# Modulator.net
KiCad netlist of a schematic drawn in Altium Designer
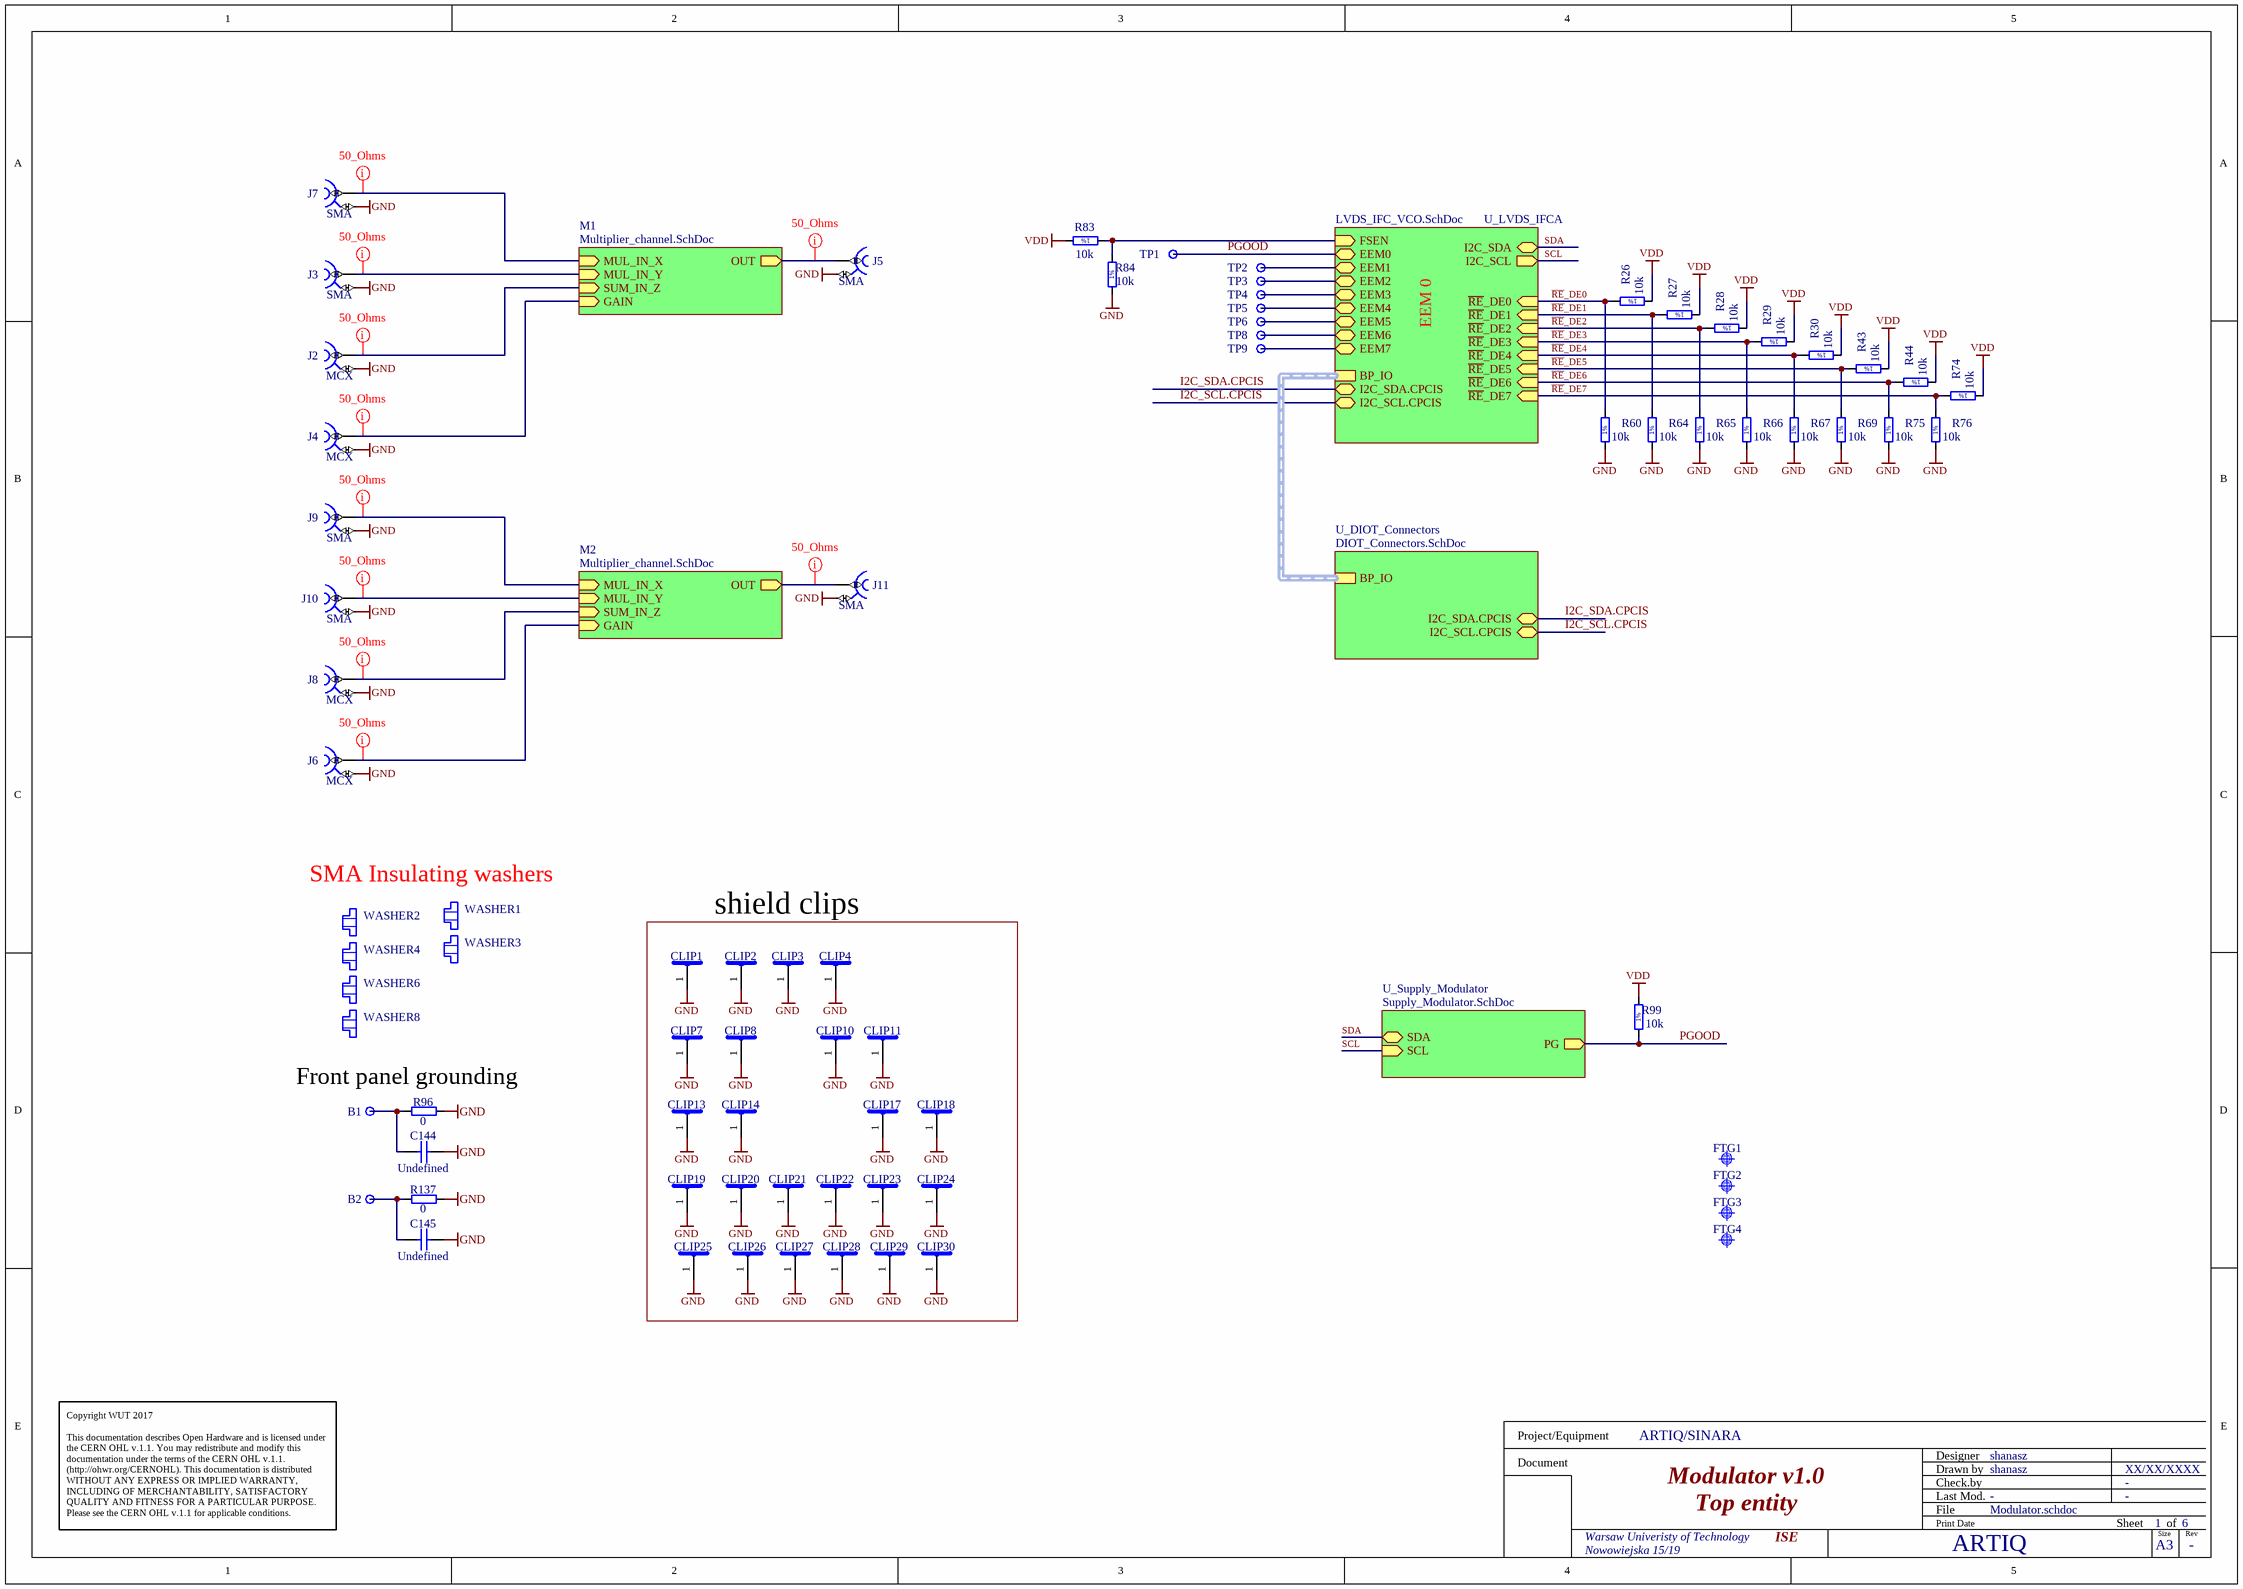
[diagram p0: Modulator.schdoc]

(export (version "E")
  (design (tool "Eeschema 10.0.6"))
  (components
    (comp (ref "B1")
      (value "Plated Hole")
      (footprint "MTG270_500")
      (description "Single Terminal Socket")
      (fields (field (name "PART NUMBER") "PLATED_HOLE2.7_PAD5.0") (field (name "AUTHOR") "CERN DEM JMW"))
      (libsource (lib "Eletro-mechanical") (part "Single Terminal Socket"))
    )
    (comp (ref "B2")
      (value "Plated Hole")
      (footprint "MTG270_500")
      (description "Single Terminal Socket")
      (fields (field (name "PART NUMBER") "PLATED_HOLE2.7_PAD5.0") (field (name "AUTHOR") "CERN DEM JMW"))
      (libsource (lib "Eletro-mechanical") (part "Single Terminal Socket"))
    )
    (comp (ref "C144")
      (value "Undefined")
      (footprint "CAPC2012X135N")
      (description "Non-polarised capacitor")
      (fields (field (name "PART NUMBER") "CC0805_NO-VALUE") (field (name "AUTHOR") "CERN DEM JLC"))
      (libsource (lib "Capacitors") (part "Capacitor - non polarized"))
    )
    (comp (ref "C145")
      (value "Undefined")
      (footprint "CAPC2012X135N")
      (description "Non-polarised capacitor")
      (fields (field (name "PART NUMBER") "CC0805_NO-VALUE") (field (name "AUTHOR") "CERN DEM JLC"))
      (libsource (lib "Capacitors") (part "Capacitor - non polarized"))
    )
    (comp (ref "CLIP1")
      (value "S1411-46R")
      (footprint "CLIP_HOLLAND-SHIELDING_LC")
      (description "Surface Mount Clip for PCB Screening Covers")
      (fields (field (name "MANUFACTURER") "HARWIN") (field (name "AUTHOR") "CERN DEM JLC"))
      (libsource (lib "LIBRARY_SCH") (part "SHIELD_CLIP"))
    )
    (comp (ref "CLIP2")
      (value "S1411-46R")
      (footprint "CLIP_HOLLAND-SHIELDING_LC")
      (description "Surface Mount Clip for PCB Screening Covers")
      (fields (field (name "MANUFACTURER") "HARWIN") (field (name "AUTHOR") "CERN DEM JLC"))
      (libsource (lib "LIBRARY_SCH") (part "SHIELD_CLIP"))
    )
    (comp (ref "CLIP3")
      (value "S1411-46R")
      (footprint "CLIP_HOLLAND-SHIELDING_LC")
      (description "Surface Mount Clip for PCB Screening Covers")
      (fields (field (name "MANUFACTURER") "HARWIN") (field (name "AUTHOR") "CERN DEM JLC"))
      (libsource (lib "LIBRARY_SCH") (part "SHIELD_CLIP"))
    )
    (comp (ref "CLIP4")
      (value "S1411-46R")
      (footprint "CLIP_HOLLAND-SHIELDING_LC")
      (description "Surface Mount Clip for PCB Screening Covers")
      (fields (field (name "MANUFACTURER") "HARWIN") (field (name "AUTHOR") "CERN DEM JLC"))
      (libsource (lib "LIBRARY_SCH") (part "SHIELD_CLIP"))
    )
    (comp (ref "CLIP7")
      (value "S1411-46R")
      (footprint "CLIP_HOLLAND-SHIELDING_LC")
      (description "Surface Mount Clip for PCB Screening Covers")
      (fields (field (name "MANUFACTURER") "HARWIN") (field (name "AUTHOR") "CERN DEM JLC"))
      (libsource (lib "LIBRARY_SCH") (part "SHIELD_CLIP"))
    )
    (comp (ref "CLIP8")
      (value "S1411-46R")
      (footprint "CLIP_HOLLAND-SHIELDING_LC")
      (description "Surface Mount Clip for PCB Screening Covers")
      (fields (field (name "MANUFACTURER") "HARWIN") (field (name "AUTHOR") "CERN DEM JLC"))
      (libsource (lib "LIBRARY_SCH") (part "SHIELD_CLIP"))
    )
    (comp (ref "CLIP10")
      (value "S1411-46R")
      (footprint "CLIP_HOLLAND-SHIELDING_LC")
      (description "Surface Mount Clip for PCB Screening Covers")
      (fields (field (name "MANUFACTURER") "HARWIN") (field (name "AUTHOR") "CERN DEM JLC"))
      (libsource (lib "LIBRARY_SCH") (part "SHIELD_CLIP"))
    )
    (comp (ref "CLIP11")
      (value "S1411-46R")
      (footprint "CLIP_HOLLAND-SHIELDING_LC")
      (description "Surface Mount Clip for PCB Screening Covers")
      (fields (field (name "MANUFACTURER") "HARWIN") (field (name "AUTHOR") "CERN DEM JLC"))
      (libsource (lib "LIBRARY_SCH") (part "SHIELD_CLIP"))
    )
    (comp (ref "CLIP13")
      (value "S1411-46R")
      (footprint "CLIP_HOLLAND-SHIELDING_LC")
      (description "Surface Mount Clip for PCB Screening Covers")
      (fields (field (name "MANUFACTURER") "HARWIN") (field (name "AUTHOR") "CERN DEM JLC"))
      (libsource (lib "LIBRARY_SCH") (part "SHIELD_CLIP"))
    )
    (comp (ref "CLIP14")
      (value "S1411-46R")
      (footprint "CLIP_HOLLAND-SHIELDING_LC")
      (description "Surface Mount Clip for PCB Screening Covers")
      (fields (field (name "MANUFACTURER") "HARWIN") (field (name "AUTHOR") "CERN DEM JLC"))
      (libsource (lib "LIBRARY_SCH") (part "SHIELD_CLIP"))
    )
    (comp (ref "CLIP17")
      (value "S1411-46R")
      (footprint "CLIP_HOLLAND-SHIELDING_LC")
      (description "Surface Mount Clip for PCB Screening Covers")
      (fields (field (name "MANUFACTURER") "HARWIN") (field (name "AUTHOR") "CERN DEM JLC"))
      (libsource (lib "LIBRARY_SCH") (part "SHIELD_CLIP"))
    )
    (comp (ref "CLIP18")
      (value "S1411-46R")
      (footprint "CLIP_HOLLAND-SHIELDING_LC")
      (description "Surface Mount Clip for PCB Screening Covers")
      (fields (field (name "MANUFACTURER") "HARWIN") (field (name "AUTHOR") "CERN DEM JLC"))
      (libsource (lib "LIBRARY_SCH") (part "SHIELD_CLIP"))
    )
    (comp (ref "CLIP19")
      (value "S1411-46R")
      (footprint "CLIP_HOLLAND-SHIELDING_LC")
      (description "Surface Mount Clip for PCB Screening Covers")
      (fields (field (name "MANUFACTURER") "HARWIN") (field (name "AUTHOR") "CERN DEM JLC"))
      (libsource (lib "LIBRARY_SCH") (part "SHIELD_CLIP"))
    )
    (comp (ref "CLIP20")
      (value "S1411-46R")
      (footprint "CLIP_HOLLAND-SHIELDING_LC")
      (description "Surface Mount Clip for PCB Screening Covers")
      (fields (field (name "MANUFACTURER") "HARWIN") (field (name "AUTHOR") "CERN DEM JLC"))
      (libsource (lib "LIBRARY_SCH") (part "SHIELD_CLIP"))
    )
    (comp (ref "CLIP21")
      (value "S1411-46R")
      (footprint "CLIP_HOLLAND-SHIELDING_LC")
      (description "Surface Mount Clip for PCB Screening Covers")
      (fields (field (name "MANUFACTURER") "HARWIN") (field (name "AUTHOR") "CERN DEM JLC"))
      (libsource (lib "LIBRARY_SCH") (part "SHIELD_CLIP"))
    )
    (comp (ref "CLIP22")
      (value "S1411-46R")
      (footprint "CLIP_HOLLAND-SHIELDING_LC")
      (description "Surface Mount Clip for PCB Screening Covers")
      (fields (field (name "MANUFACTURER") "HARWIN") (field (name "AUTHOR") "CERN DEM JLC"))
      (libsource (lib "LIBRARY_SCH") (part "SHIELD_CLIP"))
    )
    (comp (ref "CLIP23")
      (value "S1411-46R")
      (footprint "CLIP_HOLLAND-SHIELDING_LC")
      (description "Surface Mount Clip for PCB Screening Covers")
      (fields (field (name "MANUFACTURER") "HARWIN") (field (name "AUTHOR") "CERN DEM JLC"))
      (libsource (lib "LIBRARY_SCH") (part "SHIELD_CLIP"))
    )
    (comp (ref "CLIP24")
      (value "S1411-46R")
      (footprint "CLIP_HOLLAND-SHIELDING_LC")
      (description "Surface Mount Clip for PCB Screening Covers")
      (fields (field (name "MANUFACTURER") "HARWIN") (field (name "AUTHOR") "CERN DEM JLC"))
      (libsource (lib "LIBRARY_SCH") (part "SHIELD_CLIP"))
    )
    (comp (ref "CLIP25")
      (value "S1411-46R")
      (footprint "CLIP_HOLLAND-SHIELDING_LC")
      (description "Surface Mount Clip for PCB Screening Covers")
      (fields (field (name "MANUFACTURER") "HARWIN") (field (name "AUTHOR") "CERN DEM JLC"))
      (libsource (lib "LIBRARY_SCH") (part "SHIELD_CLIP"))
    )
    (comp (ref "CLIP26")
      (value "S1411-46R")
      (footprint "CLIP_HOLLAND-SHIELDING_LC")
      (description "Surface Mount Clip for PCB Screening Covers")
      (fields (field (name "MANUFACTURER") "HARWIN") (field (name "AUTHOR") "CERN DEM JLC"))
      (libsource (lib "LIBRARY_SCH") (part "SHIELD_CLIP"))
    )
    (comp (ref "CLIP27")
      (value "S1411-46R")
      (footprint "CLIP_HOLLAND-SHIELDING_LC")
      (description "Surface Mount Clip for PCB Screening Covers")
      (fields (field (name "MANUFACTURER") "HARWIN") (field (name "AUTHOR") "CERN DEM JLC"))
      (libsource (lib "LIBRARY_SCH") (part "SHIELD_CLIP"))
    )
    (comp (ref "CLIP28")
      (value "S1411-46R")
      (footprint "CLIP_HOLLAND-SHIELDING_LC")
      (description "Surface Mount Clip for PCB Screening Covers")
      (fields (field (name "MANUFACTURER") "HARWIN") (field (name "AUTHOR") "CERN DEM JLC"))
      (libsource (lib "LIBRARY_SCH") (part "SHIELD_CLIP"))
    )
    (comp (ref "CLIP29")
      (value "S1411-46R")
      (footprint "CLIP_HOLLAND-SHIELDING_LC")
      (description "Surface Mount Clip for PCB Screening Covers")
      (fields (field (name "MANUFACTURER") "HARWIN") (field (name "AUTHOR") "CERN DEM JLC"))
      (libsource (lib "LIBRARY_SCH") (part "SHIELD_CLIP"))
    )
    (comp (ref "CLIP30")
      (value "S1411-46R")
      (footprint "CLIP_HOLLAND-SHIELDING_LC")
      (description "Surface Mount Clip for PCB Screening Covers")
      (fields (field (name "MANUFACTURER") "HARWIN") (field (name "AUTHOR") "CERN DEM JLC"))
      (libsource (lib "LIBRARY_SCH") (part "SHIELD_CLIP"))
    )
    (comp (ref "FTG1")
      (value "Use only in PCB")
      (footprint "FIDUCIAL_TOP_C100-200")
      (description "Fiducial Target")
      (fields (field (name "PART NUMBER") "FIDUCIAL_TARGET_C100-200") (field (name "AUTHOR") "CERN DEM JLC"))
      (libsource (lib "Eletro-mechanical") (part "Fiducial Target"))
    )
    (comp (ref "FTG2")
      (value "Use only in PCB")
      (footprint "FIDUCIAL_TOP_S100-200")
      (description "Fiducial Target")
      (fields (field (name "PART NUMBER") "FIDUCIAL_TARGET_S100-200") (field (name "AUTHOR") "CERN DEM JLC"))
      (libsource (lib "Eletro-mechanical") (part "Fiducial Target"))
    )
    (comp (ref "FTG3")
      (value "Use only in PCB")
      (footprint "FIDUCIAL_TOP_S200-400")
      (description "Fiducial Target")
      (fields (field (name "PART NUMBER") "FIDUCIAL_TARGET_S200-400") (field (name "AUTHOR") "CERN DEM JLC"))
      (libsource (lib "Eletro-mechanical") (part "Fiducial Target"))
    )
    (comp (ref "FTG4")
      (value "Use only in PCB")
      (footprint "FIDUCIAL_TOP_S100-200")
      (description "Fiducial Target")
      (fields (field (name "PART NUMBER") "FIDUCIAL_TARGET_S100-200") (field (name "AUTHOR") "CERN DEM JLC"))
      (libsource (lib "Eletro-mechanical") (part "Fiducial Target"))
    )
    (comp (ref "J2")
      (value "MCX")
      (footprint "AMPHENOL_919-383J-51A")
      (fields
        (field (name "PART NUMBER") "AMPHENOL_919-383J-51A")
        (field (name "MANUFACTURER") "AMPHENOL")
        (field (name "MANUFACTURER PART NUMBER") "919-383J-51A")
        (field (name "AUTHOR") "CERN DEM BC")
      )
      (libsource (lib "Connectors") (part "Coax_1Female_1Shield"))
    )
    (comp (ref "J3")
      (value "SMA")
      (footprint "DELOCK_65848")
      (description "50 Ohm Through Hole SMA Right Angle PCB Jack")
      (fields
        (field (name "PART NUMBER") "DELOCK_65848")
        (field (name "MANUFACTURER") "DELOCK")
        (field (name "AUTHOR") "GK")
      )
      (libsource (lib "Modulator_pLib") (part "CON_SMA_DELOCK_65848"))
    )
    (comp (ref "J4")
      (value "MCX")
      (footprint "AMPHENOL_919-383J-51A")
      (fields
        (field (name "PART NUMBER") "AMPHENOL_919-383J-51A")
        (field (name "MANUFACTURER") "AMPHENOL")
        (field (name "MANUFACTURER PART NUMBER") "919-383J-51A")
        (field (name "AUTHOR") "CERN DEM BC")
      )
      (libsource (lib "Connectors") (part "Coax_1Female_1Shield"))
    )
    (comp (ref "J5")
      (value "SMA")
      (footprint "DELOCK_65848")
      (description "50 Ohm Through Hole SMA Right Angle PCB Jack")
      (fields
        (field (name "PART NUMBER") "DELOCK_65848")
        (field (name "MANUFACTURER") "DELOCK")
        (field (name "AUTHOR") "GK")
      )
      (libsource (lib "") (part "CON_SMA_DELOCK_65848_1"))
    )
    (comp (ref "J6")
      (value "MCX")
      (footprint "AMPHENOL_919-383J-51A")
      (fields
        (field (name "PART NUMBER") "AMPHENOL_919-383J-51A")
        (field (name "MANUFACTURER") "AMPHENOL")
        (field (name "MANUFACTURER PART NUMBER") "919-383J-51A")
        (field (name "AUTHOR") "CERN DEM BC")
      )
      (libsource (lib "Connectors") (part "Coax_1Female_1Shield"))
    )
    (comp (ref "J7")
      (value "SMA")
      (footprint "DELOCK_65848")
      (description "50 Ohm Through Hole SMA Right Angle PCB Jack")
      (fields
        (field (name "PART NUMBER") "DELOCK_65848")
        (field (name "MANUFACTURER") "DELOCK")
        (field (name "AUTHOR") "GK")
      )
      (libsource (lib "Modulator_pLib") (part "CON_SMA_DELOCK_65848"))
    )
    (comp (ref "J8")
      (value "MCX")
      (footprint "AMPHENOL_919-383J-51A")
      (fields
        (field (name "PART NUMBER") "AMPHENOL_919-383J-51A")
        (field (name "MANUFACTURER") "AMPHENOL")
        (field (name "MANUFACTURER PART NUMBER") "919-383J-51A")
        (field (name "AUTHOR") "CERN DEM BC")
      )
      (libsource (lib "Connectors") (part "Coax_1Female_1Shield"))
    )
    (comp (ref "J9")
      (value "SMA")
      (footprint "DELOCK_65848")
      (description "50 Ohm Through Hole SMA Right Angle PCB Jack")
      (fields
        (field (name "PART NUMBER") "DELOCK_65848")
        (field (name "MANUFACTURER") "DELOCK")
        (field (name "AUTHOR") "GK")
      )
      (libsource (lib "Modulator_pLib") (part "CON_SMA_DELOCK_65848"))
    )
    (comp (ref "J10")
      (value "SMA")
      (footprint "DELOCK_65848")
      (description "50 Ohm Through Hole SMA Right Angle PCB Jack")
      (fields
        (field (name "PART NUMBER") "DELOCK_65848")
        (field (name "MANUFACTURER") "DELOCK")
        (field (name "AUTHOR") "GK")
      )
      (libsource (lib "Modulator_pLib") (part "CON_SMA_DELOCK_65848"))
    )
    (comp (ref "J11")
      (value "SMA")
      (footprint "DELOCK_65848")
      (description "50 Ohm Through Hole SMA Right Angle PCB Jack")
      (fields
        (field (name "PART NUMBER") "DELOCK_65848")
        (field (name "MANUFACTURER") "DELOCK")
        (field (name "AUTHOR") "GK")
      )
      (libsource (lib "") (part "CON_SMA_DELOCK_65848_1"))
    )
    (comp (ref "R26")
      (value "10k")
      (footprint "RESC1005X40N")
      (description "Resistor - 1%")
      (fields
        (field (name "PART NUMBER") "R0402_10K_1%_0.0625W_100PPM")
        (field (name "POWER") "0.0625W")
        (field (name "AUTHOR") "CERN DEM JLC")
      )
      (libsource (lib "Resistors") (part "Resistor - 1%"))
    )
    (comp (ref "R27")
      (value "10k")
      (footprint "RESC1005X40N")
      (description "Resistor - 1%")
      (fields
        (field (name "PART NUMBER") "R0402_10K_1%_0.0625W_100PPM")
        (field (name "POWER") "0.0625W")
        (field (name "AUTHOR") "CERN DEM JLC")
      )
      (libsource (lib "Resistors") (part "Resistor - 1%"))
    )
    (comp (ref "R28")
      (value "10k")
      (footprint "RESC1005X40N")
      (description "Resistor - 1%")
      (fields
        (field (name "PART NUMBER") "R0402_10K_1%_0.0625W_100PPM")
        (field (name "POWER") "0.0625W")
        (field (name "AUTHOR") "CERN DEM JLC")
      )
      (libsource (lib "Resistors") (part "Resistor - 1%"))
    )
    (comp (ref "R29")
      (value "10k")
      (footprint "RESC1005X40N")
      (description "Resistor - 1%")
      (fields
        (field (name "PART NUMBER") "R0402_10K_1%_0.0625W_100PPM")
        (field (name "POWER") "0.0625W")
        (field (name "AUTHOR") "CERN DEM JLC")
      )
      (libsource (lib "Resistors") (part "Resistor - 1%"))
    )
    (comp (ref "R30")
      (value "10k")
      (footprint "RESC1005X40N")
      (description "Resistor - 1%")
      (fields
        (field (name "PART NUMBER") "R0402_10K_1%_0.0625W_100PPM")
        (field (name "POWER") "0.0625W")
        (field (name "AUTHOR") "CERN DEM JLC")
      )
      (libsource (lib "Resistors") (part "Resistor - 1%"))
    )
    (comp (ref "R43")
      (value "10k")
      (footprint "RESC1005X40N")
      (description "Resistor - 1%")
      (fields
        (field (name "PART NUMBER") "R0402_10K_1%_0.0625W_100PPM")
        (field (name "POWER") "0.0625W")
        (field (name "AUTHOR") "CERN DEM JLC")
      )
      (libsource (lib "Resistors") (part "Resistor - 1%"))
    )
    (comp (ref "R44")
      (value "10k")
      (footprint "RESC1005X40N")
      (description "Resistor - 1%")
      (fields
        (field (name "PART NUMBER") "R0402_10K_1%_0.0625W_100PPM")
        (field (name "POWER") "0.0625W")
        (field (name "AUTHOR") "CERN DEM JLC")
      )
      (libsource (lib "Resistors") (part "Resistor - 1%"))
    )
    (comp (ref "R60")
      (value "10k")
      (footprint "RESC1005X40N")
      (description "Resistor - 1%")
      (fields
        (field (name "PART NUMBER") "R0402_10K_1%_0.0625W_100PPM")
        (field (name "POWER") "0.0625W")
        (field (name "AUTHOR") "CERN DEM JLC")
      )
      (libsource (lib "Resistors") (part "Resistor - 1%"))
    )
    (comp (ref "R64")
      (value "10k")
      (footprint "RESC1005X40N")
      (description "Resistor - 1%")
      (fields
        (field (name "PART NUMBER") "R0402_10K_1%_0.0625W_100PPM")
        (field (name "POWER") "0.0625W")
        (field (name "AUTHOR") "CERN DEM JLC")
      )
      (libsource (lib "Resistors") (part "Resistor - 1%"))
    )
    (comp (ref "R65")
      (value "10k")
      (footprint "RESC1005X40N")
      (description "Resistor - 1%")
      (fields
        (field (name "PART NUMBER") "R0402_10K_1%_0.0625W_100PPM")
        (field (name "POWER") "0.0625W")
        (field (name "AUTHOR") "CERN DEM JLC")
      )
      (libsource (lib "Resistors") (part "Resistor - 1%"))
    )
    (comp (ref "R66")
      (value "10k")
      (footprint "RESC1005X40N")
      (description "Resistor - 1%")
      (fields
        (field (name "PART NUMBER") "R0402_10K_1%_0.0625W_100PPM")
        (field (name "POWER") "0.0625W")
        (field (name "AUTHOR") "CERN DEM JLC")
      )
      (libsource (lib "Resistors") (part "Resistor - 1%"))
    )
    (comp (ref "R67")
      (value "10k")
      (footprint "RESC1005X40N")
      (description "Resistor - 1%")
      (fields
        (field (name "PART NUMBER") "R0402_10K_1%_0.0625W_100PPM")
        (field (name "POWER") "0.0625W")
        (field (name "AUTHOR") "CERN DEM JLC")
      )
      (libsource (lib "Resistors") (part "Resistor - 1%"))
    )
    (comp (ref "R69")
      (value "10k")
      (footprint "RESC1005X40N")
      (description "Resistor - 1%")
      (fields
        (field (name "PART NUMBER") "R0402_10K_1%_0.0625W_100PPM")
        (field (name "POWER") "0.0625W")
        (field (name "AUTHOR") "CERN DEM JLC")
      )
      (libsource (lib "Resistors") (part "Resistor - 1%"))
    )
    (comp (ref "R74")
      (value "10k")
      (footprint "RESC1005X40N")
      (description "Resistor - 1%")
      (fields
        (field (name "PART NUMBER") "R0402_10K_1%_0.0625W_100PPM")
        (field (name "POWER") "0.0625W")
        (field (name "AUTHOR") "CERN DEM JLC")
      )
      (libsource (lib "Resistors") (part "Resistor - 1%"))
    )
    (comp (ref "R75")
      (value "10k")
      (footprint "RESC1005X40N")
      (description "Resistor - 1%")
      (fields
        (field (name "PART NUMBER") "R0402_10K_1%_0.0625W_100PPM")
        (field (name "POWER") "0.0625W")
        (field (name "AUTHOR") "CERN DEM JLC")
      )
      (libsource (lib "Resistors") (part "Resistor - 1%"))
    )
    (comp (ref "R76")
      (value "10k")
      (footprint "RESC1005X40N")
      (description "Resistor - 1%")
      (fields
        (field (name "PART NUMBER") "R0402_10K_1%_0.0625W_100PPM")
        (field (name "POWER") "0.0625W")
        (field (name "AUTHOR") "CERN DEM JLC")
      )
      (libsource (lib "Resistors") (part "Resistor - 1%"))
    )
    (comp (ref "R83")
      (value "10k")
      (footprint "RESC1005X40N")
      (description "Resistor - 1%")
      (fields
        (field (name "PART NUMBER") "R0402_10K_1%_0.0625W_100PPM")
        (field (name "POWER") "0.0625W")
        (field (name "AUTHOR") "CERN DEM JLC")
      )
      (libsource (lib "Resistors") (part "Resistor - 1%"))
    )
    (comp (ref "R84")
      (value "10k")
      (footprint "RESC1005X40N")
      (description "Resistor - 1%")
      (fields
        (field (name "PART NUMBER") "R0402_10K_1%_0.0625W_100PPM")
        (field (name "POWER") "0.0625W")
        (field (name "AUTHOR") "CERN DEM JLC")
      )
      (libsource (lib "Resistors") (part "Resistor - 1%"))
    )
    (comp (ref "R96")
      (value "0")
      (footprint "RESC1608X55N")
      (description "Resistor")
      (fields
        (field (name "PART NUMBER") "R0603_0R_JUMPER")
        (field (name "MANUFACTURER") "GENERIC")
        (field (name "AUTHOR") "CERN DEM JLC")
      )
      (libsource (lib "Resistors") (part "Resistor"))
    )
    (comp (ref "R99")
      (value "10k")
      (footprint "RESC1005X40N")
      (description "Resistor - 1%")
      (fields
        (field (name "PART NUMBER") "R0402_10K_1%_0.0625W_100PPM")
        (field (name "POWER") "0.0625W")
        (field (name "AUTHOR") "CERN DEM JLC")
      )
      (libsource (lib "Resistors") (part "Resistor - 1%"))
    )
    (comp (ref "R137")
      (value "0")
      (footprint "RESC1608X55N")
      (description "Resistor")
      (fields
        (field (name "PART NUMBER") "R0603_0R_JUMPER")
        (field (name "MANUFACTURER") "GENERIC")
        (field (name "AUTHOR") "CERN DEM JLC")
      )
      (libsource (lib "Resistors") (part "Resistor"))
    )
    (comp (ref "TP1")
      (value "Test Point")
      (footprint "TPS127")
      (fields (field (name "PART NUMBER") "SMD_PAD_1.27X1.27MM") (field (name "AUTHOR") "CERN DEM JLC"))
      (libsource (lib "Eletro-mechanical") (part "Test Point"))
    )
    (comp (ref "TP2")
      (value "Test Point")
      (footprint "TPS127")
      (fields (field (name "PART NUMBER") "SMD_PAD_1.27X1.27MM") (field (name "AUTHOR") "CERN DEM JLC"))
      (libsource (lib "Eletro-mechanical") (part "Test Point"))
    )
    (comp (ref "TP3")
      (value "Test Point")
      (footprint "TPS127")
      (fields (field (name "PART NUMBER") "SMD_PAD_1.27X1.27MM") (field (name "AUTHOR") "CERN DEM JLC"))
      (libsource (lib "Eletro-mechanical") (part "Test Point"))
    )
    (comp (ref "TP4")
      (value "Test Point")
      (footprint "TPS127")
      (fields (field (name "PART NUMBER") "SMD_PAD_1.27X1.27MM") (field (name "AUTHOR") "CERN DEM JLC"))
      (libsource (lib "Eletro-mechanical") (part "Test Point"))
    )
    (comp (ref "TP5")
      (value "Test Point")
      (footprint "TPS127")
      (fields (field (name "PART NUMBER") "SMD_PAD_1.27X1.27MM") (field (name "AUTHOR") "CERN DEM JLC"))
      (libsource (lib "Eletro-mechanical") (part "Test Point"))
    )
    (comp (ref "TP6")
      (value "Test Point")
      (footprint "TPS127")
      (fields (field (name "PART NUMBER") "SMD_PAD_1.27X1.27MM") (field (name "AUTHOR") "CERN DEM JLC"))
      (libsource (lib "Eletro-mechanical") (part "Test Point"))
    )
    (comp (ref "TP8")
      (value "Test Point")
      (footprint "TPS127")
      (fields (field (name "PART NUMBER") "SMD_PAD_1.27X1.27MM") (field (name "AUTHOR") "CERN DEM JLC"))
      (libsource (lib "Eletro-mechanical") (part "Test Point"))
    )
    (comp (ref "TP9")
      (value "Test Point")
      (footprint "TPS127")
      (fields (field (name "PART NUMBER") "SMD_PAD_1.27X1.27MM") (field (name "AUTHOR") "CERN DEM JLC"))
      (libsource (lib "Eletro-mechanical") (part "Test Point"))
    )
    (comp (ref "WASHER1")
      (value "~")
      (footprint "Keystone_7687")
      (description "SMA_Shoulder Washer")
      (fields
        (field (name "PART NUMBER") "custom 3D printed")
        (field (name "MANUFACTURER") "custom")
        (field (name "AUTHOR") "GK")
      )
      (libsource (lib "Modulator_pLib") (part "Keystone_7687"))
    )
    (comp (ref "WASHER2")
      (value "~")
      (footprint "Keystone_7687")
      (description "SMA_Shoulder Washer")
      (fields
        (field (name "PART NUMBER") "custom 3D printed")
        (field (name "MANUFACTURER") "custom")
        (field (name "AUTHOR") "GK")
      )
      (libsource (lib "Modulator_pLib") (part "Keystone_7687"))
    )
    (comp (ref "WASHER3")
      (value "~")
      (footprint "Keystone_7687")
      (description "SMA_Shoulder Washer")
      (fields
        (field (name "PART NUMBER") "custom 3D printed")
        (field (name "MANUFACTURER") "custom")
        (field (name "AUTHOR") "GK")
      )
      (libsource (lib "Modulator_pLib") (part "Keystone_7687"))
    )
    (comp (ref "WASHER4")
      (value "~")
      (footprint "Keystone_7687")
      (description "SMA_Shoulder Washer")
      (fields
        (field (name "PART NUMBER") "custom 3D printed")
        (field (name "MANUFACTURER") "custom")
        (field (name "AUTHOR") "GK")
      )
      (libsource (lib "Modulator_pLib") (part "Keystone_7687"))
    )
    (comp (ref "WASHER6")
      (value "~")
      (footprint "Keystone_7687")
      (description "SMA_Shoulder Washer")
      (fields
        (field (name "PART NUMBER") "custom 3D printed")
        (field (name "MANUFACTURER") "custom")
        (field (name "AUTHOR") "GK")
      )
      (libsource (lib "Modulator_pLib") (part "Keystone_7687"))
    )
    (comp (ref "WASHER8")
      (value "~")
      (footprint "Keystone_7687")
      (description "SMA_Shoulder Washer")
      (fields
        (field (name "PART NUMBER") "custom 3D printed")
        (field (name "MANUFACTURER") "custom")
        (field (name "AUTHOR") "GK")
      )
      (libsource (lib "Modulator_pLib") (part "Keystone_7687"))
    )
  )
  (nets
    (net (code "2") (name "/EEM1") (class "Default")
      (node (ref "TP2") (pin "1") (pinfunction "1_1") (pintype "bidirectional"))
    )
    (net (code "3") (name "/EEM2") (class "Default")
      (node (ref "TP3") (pin "1") (pinfunction "1_1") (pintype "bidirectional"))
    )
    (net (code "4") (name "/EEM3") (class "Default")
      (node (ref "TP4") (pin "1") (pinfunction "1_1") (pintype "bidirectional"))
    )
    (net (code "5") (name "/EEM4") (class "Default")
      (node (ref "TP5") (pin "1") (pinfunction "1_1") (pintype "bidirectional"))
    )
    (net (code "6") (name "/EEM5") (class "Default")
      (node (ref "TP6") (pin "1") (pinfunction "1_1") (pintype "bidirectional"))
    )
    (net (code "7") (name "/EEM6") (class "Default")
      (node (ref "TP8") (pin "1") (pinfunction "1_1") (pintype "bidirectional"))
    )
    (net (code "8") (name "/EEM7") (class "Default")
      (node (ref "TP9") (pin "1") (pinfunction "1_1") (pintype "bidirectional"))
    )
    (net (code "9") (name "/FSEN") (class "Default")
      (node (ref "R83") (pin "2") (pinfunction "2_2") (pintype "passive"))
      (node (ref "R84") (pin "2") (pinfunction "2_2") (pintype "passive"))
    )
    (net (code "10") (name "/GAIN") (class "Default")
      (node (ref "J6") (pin "1") (pinfunction "1_1") (pintype "bidirectional"))
    )
    (net (code "11") (name "/GAIN_1") (class "Default")
      (node (ref "J4") (pin "1") (pinfunction "1_1") (pintype "bidirectional"))
    )
    (net (code "14") (name "/MUL_IN_X") (class "Default")
      (node (ref "J7") (pin "1") (pinfunction "1_1") (pintype "bidirectional"))
    )
    (net (code "15") (name "/MUL_IN_X_1") (class "Default")
      (node (ref "J9") (pin "1") (pinfunction "1_1") (pintype "bidirectional"))
    )
    (net (code "16") (name "/MUL_IN_Y") (class "Default")
      (node (ref "J3") (pin "1") (pinfunction "1_1") (pintype "bidirectional"))
    )
    (net (code "17") (name "/MUL_IN_Y_1") (class "Default")
      (node (ref "J10") (pin "1") (pinfunction "1_1") (pintype "bidirectional"))
    )
    (net (code "18") (name "/OUT") (class "Default")
      (node (ref "J5") (pin "1") (pinfunction "1_1") (pintype "bidirectional"))
    )
    (net (code "19") (name "/OUT_1") (class "Default")
      (node (ref "J11") (pin "1") (pinfunction "1_1") (pintype "bidirectional"))
    )
    (net (code "20") (name "/PGOOD") (class "Default")
      (node (ref "R99") (pin "1") (pinfunction "1_1") (pintype "passive"))
      (node (ref "TP1") (pin "1") (pinfunction "1_1") (pintype "bidirectional"))
    )
    (net (code "23") (name "/SUM_IN_Z") (class "Default")
      (node (ref "J2") (pin "1") (pinfunction "1_1") (pintype "bidirectional"))
    )
    (net (code "24") (name "/SUM_IN_Z_1") (class "Default")
      (node (ref "J8") (pin "1") (pinfunction "1_1") (pintype "bidirectional"))
    )
    (net (code "25") (name "/~{RE}_DE0") (class "Default")
      (node (ref "R26") (pin "2") (pinfunction "2_2") (pintype "passive"))
      (node (ref "R60") (pin "2") (pinfunction "2_2") (pintype "passive"))
    )
    (net (code "26") (name "/~{RE}_DE1") (class "Default")
      (node (ref "R27") (pin "2") (pinfunction "2_2") (pintype "passive"))
      (node (ref "R64") (pin "2") (pinfunction "2_2") (pintype "passive"))
    )
    (net (code "27") (name "/~{RE}_DE2") (class "Default")
      (node (ref "R28") (pin "2") (pinfunction "2_2") (pintype "passive"))
      (node (ref "R65") (pin "2") (pinfunction "2_2") (pintype "passive"))
    )
    (net (code "28") (name "/~{RE}_DE3") (class "Default")
      (node (ref "R29") (pin "2") (pinfunction "2_2") (pintype "passive"))
      (node (ref "R66") (pin "2") (pinfunction "2_2") (pintype "passive"))
    )
    (net (code "29") (name "/~{RE}_DE4") (class "Default")
      (node (ref "R30") (pin "2") (pinfunction "2_2") (pintype "passive"))
      (node (ref "R67") (pin "2") (pinfunction "2_2") (pintype "passive"))
    )
    (net (code "30") (name "/~{RE}_DE5") (class "Default")
      (node (ref "R43") (pin "2") (pinfunction "2_2") (pintype "passive"))
      (node (ref "R69") (pin "2") (pinfunction "2_2") (pintype "passive"))
    )
    (net (code "31") (name "/~{RE}_DE6") (class "Default")
      (node (ref "R44") (pin "2") (pinfunction "2_2") (pintype "passive"))
      (node (ref "R75") (pin "2") (pinfunction "2_2") (pintype "passive"))
    )
    (net (code "32") (name "/~{RE}_DE7") (class "Default")
      (node (ref "R74") (pin "2") (pinfunction "2_2") (pintype "passive"))
      (node (ref "R76") (pin "2") (pinfunction "2_2") (pintype "passive"))
    )
    (net (code "33") (name "GND") (class "Default")
      (node (ref "C144") (pin "2") (pinfunction "2_2") (pintype "passive"))
      (node (ref "C145") (pin "2") (pinfunction "2_2") (pintype "passive"))
      (node (ref "CLIP1") (pin "1") (pinfunction "1_1") (pintype "passive"))
      (node (ref "CLIP10") (pin "1") (pinfunction "1_1") (pintype "passive"))
      (node (ref "CLIP11") (pin "1") (pinfunction "1_1") (pintype "passive"))
      (node (ref "CLIP13") (pin "1") (pinfunction "1_1") (pintype "passive"))
      (node (ref "CLIP14") (pin "1") (pinfunction "1_1") (pintype "passive"))
      (node (ref "CLIP17") (pin "1") (pinfunction "1_1") (pintype "passive"))
      (node (ref "CLIP18") (pin "1") (pinfunction "1_1") (pintype "passive"))
      (node (ref "CLIP19") (pin "1") (pinfunction "1_1") (pintype "passive"))
      (node (ref "CLIP2") (pin "1") (pinfunction "1_1") (pintype "passive"))
      (node (ref "CLIP20") (pin "1") (pinfunction "1_1") (pintype "passive"))
      (node (ref "CLIP21") (pin "1") (pinfunction "1_1") (pintype "passive"))
      (node (ref "CLIP22") (pin "1") (pinfunction "1_1") (pintype "passive"))
      (node (ref "CLIP23") (pin "1") (pinfunction "1_1") (pintype "passive"))
      (node (ref "CLIP24") (pin "1") (pinfunction "1_1") (pintype "passive"))
      (node (ref "CLIP25") (pin "1") (pinfunction "1_1") (pintype "passive"))
      (node (ref "CLIP26") (pin "1") (pinfunction "1_1") (pintype "passive"))
      (node (ref "CLIP27") (pin "1") (pinfunction "1_1") (pintype "passive"))
      (node (ref "CLIP28") (pin "1") (pinfunction "1_1") (pintype "passive"))
      (node (ref "CLIP29") (pin "1") (pinfunction "1_1") (pintype "passive"))
      (node (ref "CLIP3") (pin "1") (pinfunction "1_1") (pintype "passive"))
      (node (ref "CLIP30") (pin "1") (pinfunction "1_1") (pintype "passive"))
      (node (ref "CLIP4") (pin "1") (pinfunction "1_1") (pintype "passive"))
      (node (ref "CLIP7") (pin "1") (pinfunction "1_1") (pintype "passive"))
      (node (ref "CLIP8") (pin "1") (pinfunction "1_1") (pintype "passive"))
      (node (ref "J10") (pin "2") (pinfunction "2_2") (pintype "bidirectional"))
      (node (ref "J11") (pin "2") (pinfunction "2_2") (pintype "bidirectional"))
      (node (ref "J2") (pin "2") (pinfunction "2_2") (pintype "bidirectional"))
      (node (ref "J3") (pin "2") (pinfunction "2_2") (pintype "bidirectional"))
      (node (ref "J4") (pin "2") (pinfunction "2_2") (pintype "bidirectional"))
      (node (ref "J5") (pin "2") (pinfunction "2_2") (pintype "bidirectional"))
      (node (ref "J6") (pin "2") (pinfunction "2_2") (pintype "bidirectional"))
      (node (ref "J7") (pin "2") (pinfunction "2_2") (pintype "bidirectional"))
      (node (ref "J8") (pin "2") (pinfunction "2_2") (pintype "bidirectional"))
      (node (ref "J9") (pin "2") (pinfunction "2_2") (pintype "bidirectional"))
      (node (ref "R137") (pin "2") (pinfunction "2_2") (pintype "passive"))
      (node (ref "R60") (pin "1") (pinfunction "1_1") (pintype "passive"))
      (node (ref "R64") (pin "1") (pinfunction "1_1") (pintype "passive"))
      (node (ref "R65") (pin "1") (pinfunction "1_1") (pintype "passive"))
      (node (ref "R66") (pin "1") (pinfunction "1_1") (pintype "passive"))
      (node (ref "R67") (pin "1") (pinfunction "1_1") (pintype "passive"))
      (node (ref "R69") (pin "1") (pinfunction "1_1") (pintype "passive"))
      (node (ref "R75") (pin "1") (pinfunction "1_1") (pintype "passive"))
      (node (ref "R76") (pin "1") (pinfunction "1_1") (pintype "passive"))
      (node (ref "R84") (pin "1") (pinfunction "1_1") (pintype "passive"))
      (node (ref "R96") (pin "2") (pinfunction "2_2") (pintype "passive"))
    )
    (net (code "34") (name "Net-(B1-Pad1)") (class "Default")
      (node (ref "B1") (pin "1") (pinfunction "1_1") (pintype "bidirectional"))
      (node (ref "C144") (pin "1") (pinfunction "1_1") (pintype "passive"))
      (node (ref "R96") (pin "1") (pinfunction "1_1") (pintype "passive"))
    )
    (net (code "35") (name "Net-(B2-Pad1)") (class "Default")
      (node (ref "B2") (pin "1") (pinfunction "1_1") (pintype "bidirectional"))
      (node (ref "C145") (pin "1") (pinfunction "1_1") (pintype "passive"))
      (node (ref "R137") (pin "1") (pinfunction "1_1") (pintype "passive"))
    )
    (net (code "36") (name "VDD") (class "Default")
      (node (ref "R26") (pin "1") (pinfunction "1_1") (pintype "passive"))
      (node (ref "R27") (pin "1") (pinfunction "1_1") (pintype "passive"))
      (node (ref "R28") (pin "1") (pinfunction "1_1") (pintype "passive"))
      (node (ref "R29") (pin "1") (pinfunction "1_1") (pintype "passive"))
      (node (ref "R30") (pin "1") (pinfunction "1_1") (pintype "passive"))
      (node (ref "R43") (pin "1") (pinfunction "1_1") (pintype "passive"))
      (node (ref "R44") (pin "1") (pinfunction "1_1") (pintype "passive"))
      (node (ref "R74") (pin "1") (pinfunction "1_1") (pintype "passive"))
      (node (ref "R83") (pin "1") (pinfunction "1_1") (pintype "passive"))
      (node (ref "R99") (pin "2") (pinfunction "2_2") (pintype "passive"))
    )
  )
)
